# other.net
KiCad netlist of a schematic drawn in Altium Designer
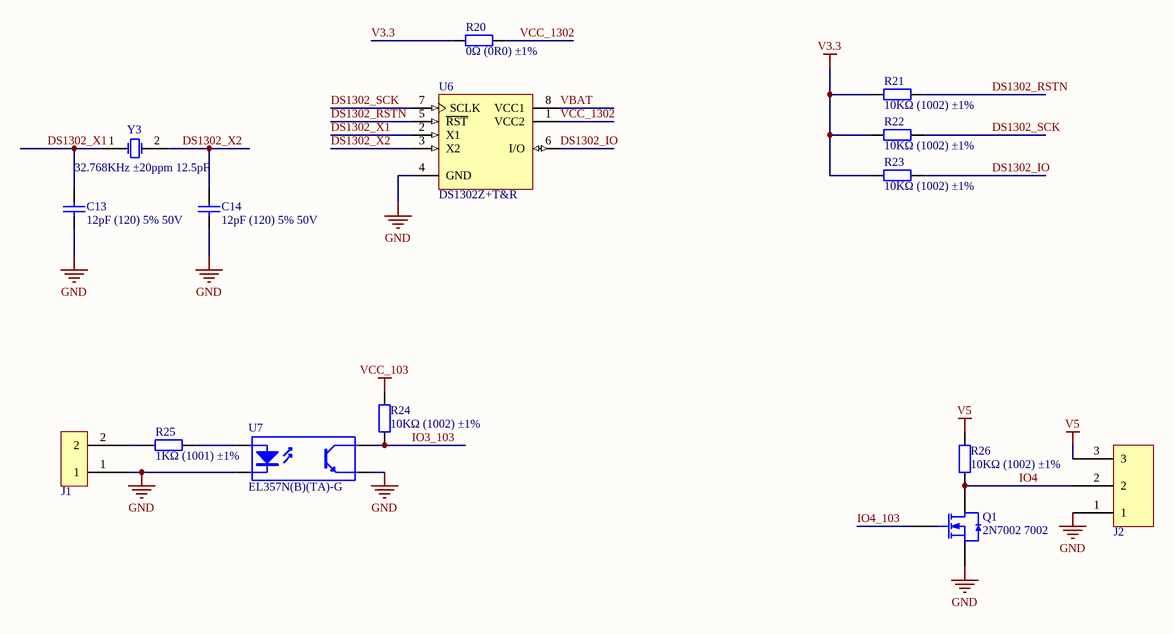
[diagram p0: other.SchDoc]

(export (version "E")
  (design (tool "Eeschema 10.0.6"))
  (components
    (comp (ref "C13")
      (value "12pF (120) 5% 50V")
      (footprint "0603_C")
      (description "贴片电容")
      (libsource (lib "Miscellaneous Devices LC") (part "0603 12pF (120) 5% 50V"))
    )
    (comp (ref "C14")
      (value "12pF (120) 5% 50V")
      (footprint "0603_C")
      (description "贴片电容")
      (libsource (lib "Miscellaneous Devices LC") (part "0603 12pF (120) 5% 50V"))
    )
    (comp (ref "J1") (value "KF301-2P") (footprint "KF301-2P") (libsource (lib "CHK-I") (part "KF301-2P")))
    (comp (ref "J2") (value "KF301-3P") (footprint "KF301-3P") (libsource (lib "CHK-I") (part "KF301-3P")))
    (comp (ref "Q1")
      (value "2N7002 7002")
      (footprint "SOT-23(SOT-23-3)")
      (description "MOS(场效应管)")
      (libsource (lib "Miscellaneous Devices LC") (part "2N7002 7002"))
    )
    (comp (ref "R20")
      (value "0Ω (0R0) ±1%")
      (footprint "1206_R")
      (description "贴片电阻")
      (libsource (lib "Miscellaneous Devices LC") (part "1206 0Ω (0R0) 1%"))
    )
    (comp (ref "R21")
      (value "10KΩ (1002) ±1%")
      (footprint "0603_R")
      (description "贴片电阻")
      (libsource (lib "Miscellaneous Devices LC") (part "0603 10KΩ (1002) 1%"))
    )
    (comp (ref "R22")
      (value "10KΩ (1002) ±1%")
      (footprint "0603_R")
      (description "贴片电阻")
      (libsource (lib "Miscellaneous Devices LC") (part "0603 10KΩ (1002) 1%"))
    )
    (comp (ref "R23")
      (value "10KΩ (1002) ±1%")
      (footprint "0603_R")
      (description "贴片电阻")
      (libsource (lib "Miscellaneous Devices LC") (part "0603 10KΩ (1002) 1%"))
    )
    (comp (ref "R24")
      (value "10KΩ (1002) ±1%")
      (footprint "1206_R")
      (description "贴片电阻")
      (libsource (lib "Miscellaneous Devices LC") (part "1206 10KΩ (1002) 1%"))
    )
    (comp (ref "R25")
      (value "1KΩ (1001) ±1%")
      (footprint "1206_R")
      (description "贴片电阻")
      (libsource (lib "Miscellaneous Devices LC") (part "1206 1KΩ (1001) 1%"))
    )
    (comp (ref "R26")
      (value "10KΩ (1002) ±1%")
      (footprint "1206_R")
      (description "贴片电阻")
      (libsource (lib "Miscellaneous Devices LC") (part "1206 10KΩ (1002) 1%"))
    )
    (comp (ref "U6")
      (value "DS1302Z+T&R")
      (footprint "SOIC-8_150mil")
      (description "实时时钟")
      (libsource (lib "Miscellaneous Devices LC") (part "DS1302Z+T&R_[C8959]"))
    )
    (comp (ref "U7")
      (value "EL357N(B)(TA)-G")
      (footprint "SOP-4_P2.54")
      (description "贴片光耦")
      (libsource (lib "Miscellaneous Devices LC") (part "EL357N(B)(TA)-G_[C6649]"))
    )
    (comp (ref "Y3")
      (value "32.768KHz ±20ppm 12.5pF")
      (footprint "SMD-3215_2P FC - 135")
      (description "贴片晶振")
      (libsource (lib "Miscellaneous Devices LC") (part "SMD-3215_2P 32.768KHz 20ppm 12.5pF"))
    )
  )
  (nets
    (net (code "1") (name "/DS1302_IO") (class "Default")
      (node (ref "R23") (pin "2") (pinfunction "2_2") (pintype "passive"))
      (node (ref "U6") (pin "6") (pinfunction "I/O_6") (pintype "bidirectional"))
    )
    (net (code "2") (name "/DS1302_RSTN") (class "Default")
      (node (ref "R21") (pin "2") (pinfunction "2_2") (pintype "passive"))
      (node (ref "U6") (pin "5") (pinfunction "~{RST}_5") (pintype "input"))
    )
    (net (code "3") (name "/DS1302_SCK") (class "Default")
      (node (ref "R22") (pin "2") (pinfunction "2_2") (pintype "passive"))
      (node (ref "U6") (pin "7") (pinfunction "SCLK_7") (pintype "input"))
    )
    (net (code "4") (name "/DS1302_X1") (class "Default")
      (node (ref "C13") (pin "2") (pinfunction "2_2") (pintype "passive"))
      (node (ref "U6") (pin "2") (pinfunction "X1_2") (pintype "input"))
      (node (ref "Y3") (pin "1") (pinfunction "OSC1_1") (pintype "passive"))
    )
    (net (code "5") (name "/DS1302_X2") (class "Default")
      (node (ref "C14") (pin "2") (pinfunction "2_2") (pintype "passive"))
      (node (ref "U6") (pin "3") (pinfunction "X2_3") (pintype "input"))
      (node (ref "Y3") (pin "2") (pinfunction "OSC2_2") (pintype "passive"))
    )
    (net (code "6") (name "/IO3_103") (class "Default")
      (node (ref "R24") (pin "1") (pinfunction "1_1") (pintype "passive"))
      (node (ref "U7") (pin "4") (pinfunction "C_4") (pintype "passive"))
    )
    (net (code "7") (name "/IO4") (class "Default")
      (node (ref "J2") (pin "2") (pinfunction "2_2") (pintype "passive"))
      (node (ref "Q1") (pin "3") (pinfunction "D_3") (pintype "passive"))
      (node (ref "R26") (pin "1") (pinfunction "1_1") (pintype "passive"))
    )
    (net (code "8") (name "/IO4_103") (class "Default")
      (node (ref "Q1") (pin "1") (pinfunction "G_1") (pintype "passive"))
    )
    (net (code "9") (name "/VBAT") (class "Default")
      (node (ref "U6") (pin "8") (pinfunction "VCC1_8") (pintype "power_in"))
    )
    (net (code "10") (name "/VCC_1302") (class "Default")
      (node (ref "R20") (pin "2") (pinfunction "2_2") (pintype "passive"))
      (node (ref "U6") (pin "1") (pinfunction "VCC2_1") (pintype "power_in"))
    )
    (net (code "11") (name "GND") (class "Default")
      (node (ref "C13") (pin "1") (pinfunction "1_1") (pintype "passive"))
      (node (ref "C14") (pin "1") (pinfunction "1_1") (pintype "passive"))
      (node (ref "J1") (pin "1") (pinfunction "1_1") (pintype "passive"))
      (node (ref "J2") (pin "1") (pinfunction "1_1") (pintype "passive"))
      (node (ref "Q1") (pin "2") (pinfunction "S_2") (pintype "passive"))
      (node (ref "U6") (pin "4") (pinfunction "GND_4") (pintype "power_in"))
      (node (ref "U7") (pin "2") (pinfunction "K_2") (pintype "passive"))
      (node (ref "U7") (pin "3") (pinfunction "E_3") (pintype "passive"))
    )
    (net (code "12") (name "Net-(J1-Pad2)") (class "Default")
      (node (ref "J1") (pin "2") (pinfunction "2_2") (pintype "passive"))
      (node (ref "R25") (pin "1") (pinfunction "1_1") (pintype "passive"))
    )
    (net (code "13") (name "Net-(U7-A)") (class "Default")
      (node (ref "R25") (pin "2") (pinfunction "2_2") (pintype "passive"))
      (node (ref "U7") (pin "1") (pinfunction "A_1") (pintype "passive"))
    )
    (net (code "14") (name "V3.3") (class "Default")
      (node (ref "R20") (pin "1") (pinfunction "1_1") (pintype "passive"))
      (node (ref "R21") (pin "1") (pinfunction "1_1") (pintype "passive"))
      (node (ref "R22") (pin "1") (pinfunction "1_1") (pintype "passive"))
      (node (ref "R23") (pin "1") (pinfunction "1_1") (pintype "passive"))
    )
    (net (code "15") (name "V5") (class "Default")
      (node (ref "J2") (pin "3") (pinfunction "3_3") (pintype "passive"))
      (node (ref "R26") (pin "2") (pinfunction "2_2") (pintype "passive"))
    )
    (net (code "16") (name "VCC_103") (class "Default")
      (node (ref "R24") (pin "2") (pinfunction "2_2") (pintype "passive"))
    )
  )
)
